# RK05TA.net
KiCad netlist of a schematic drawn in EAGLE
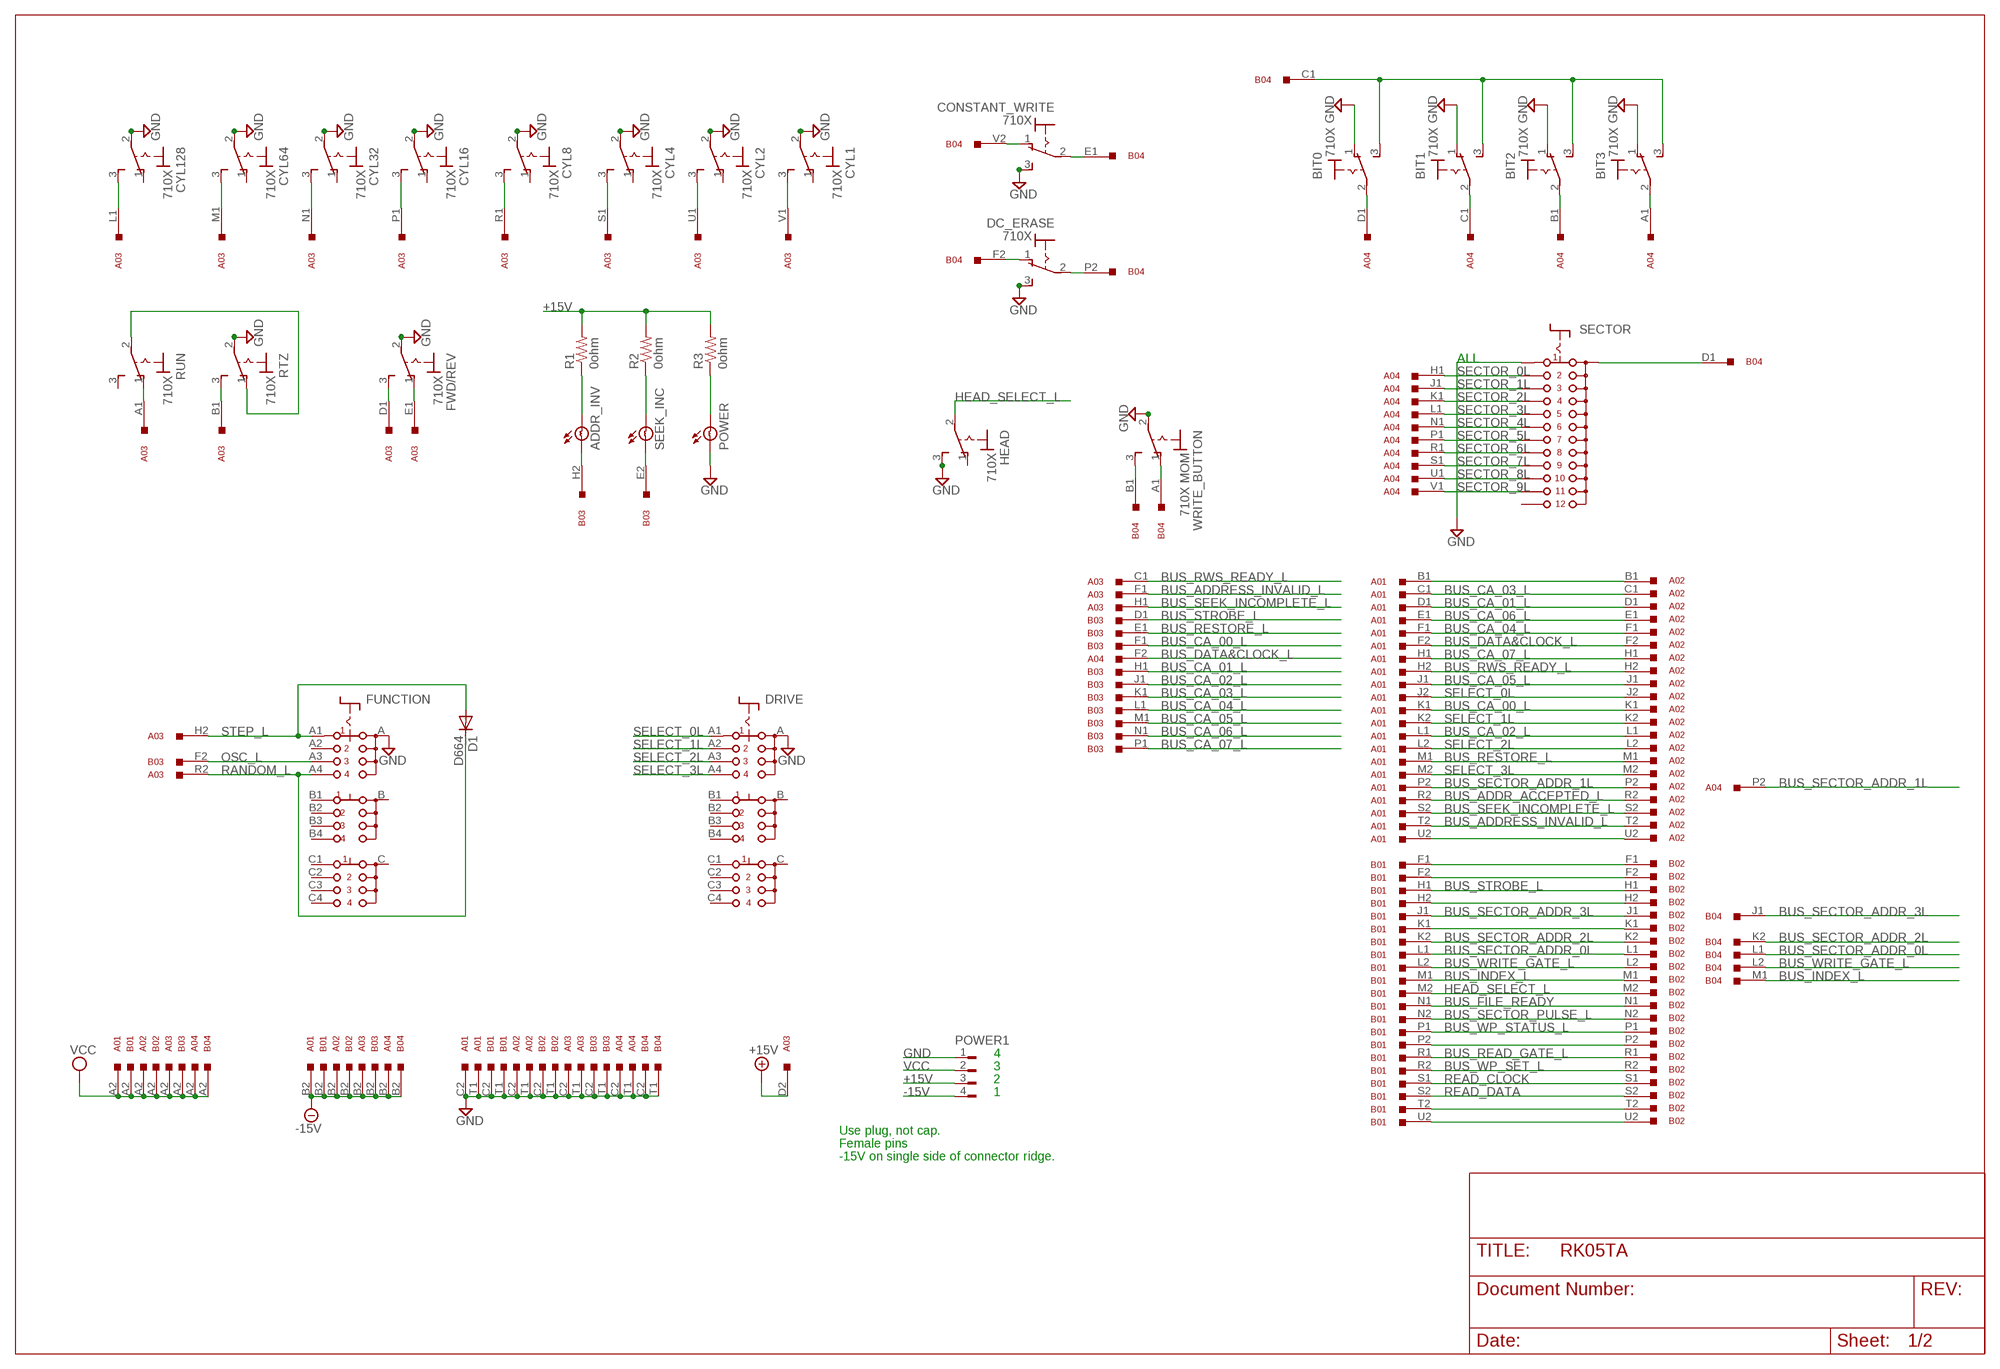
[diagram p0: schematic, sheet 1]
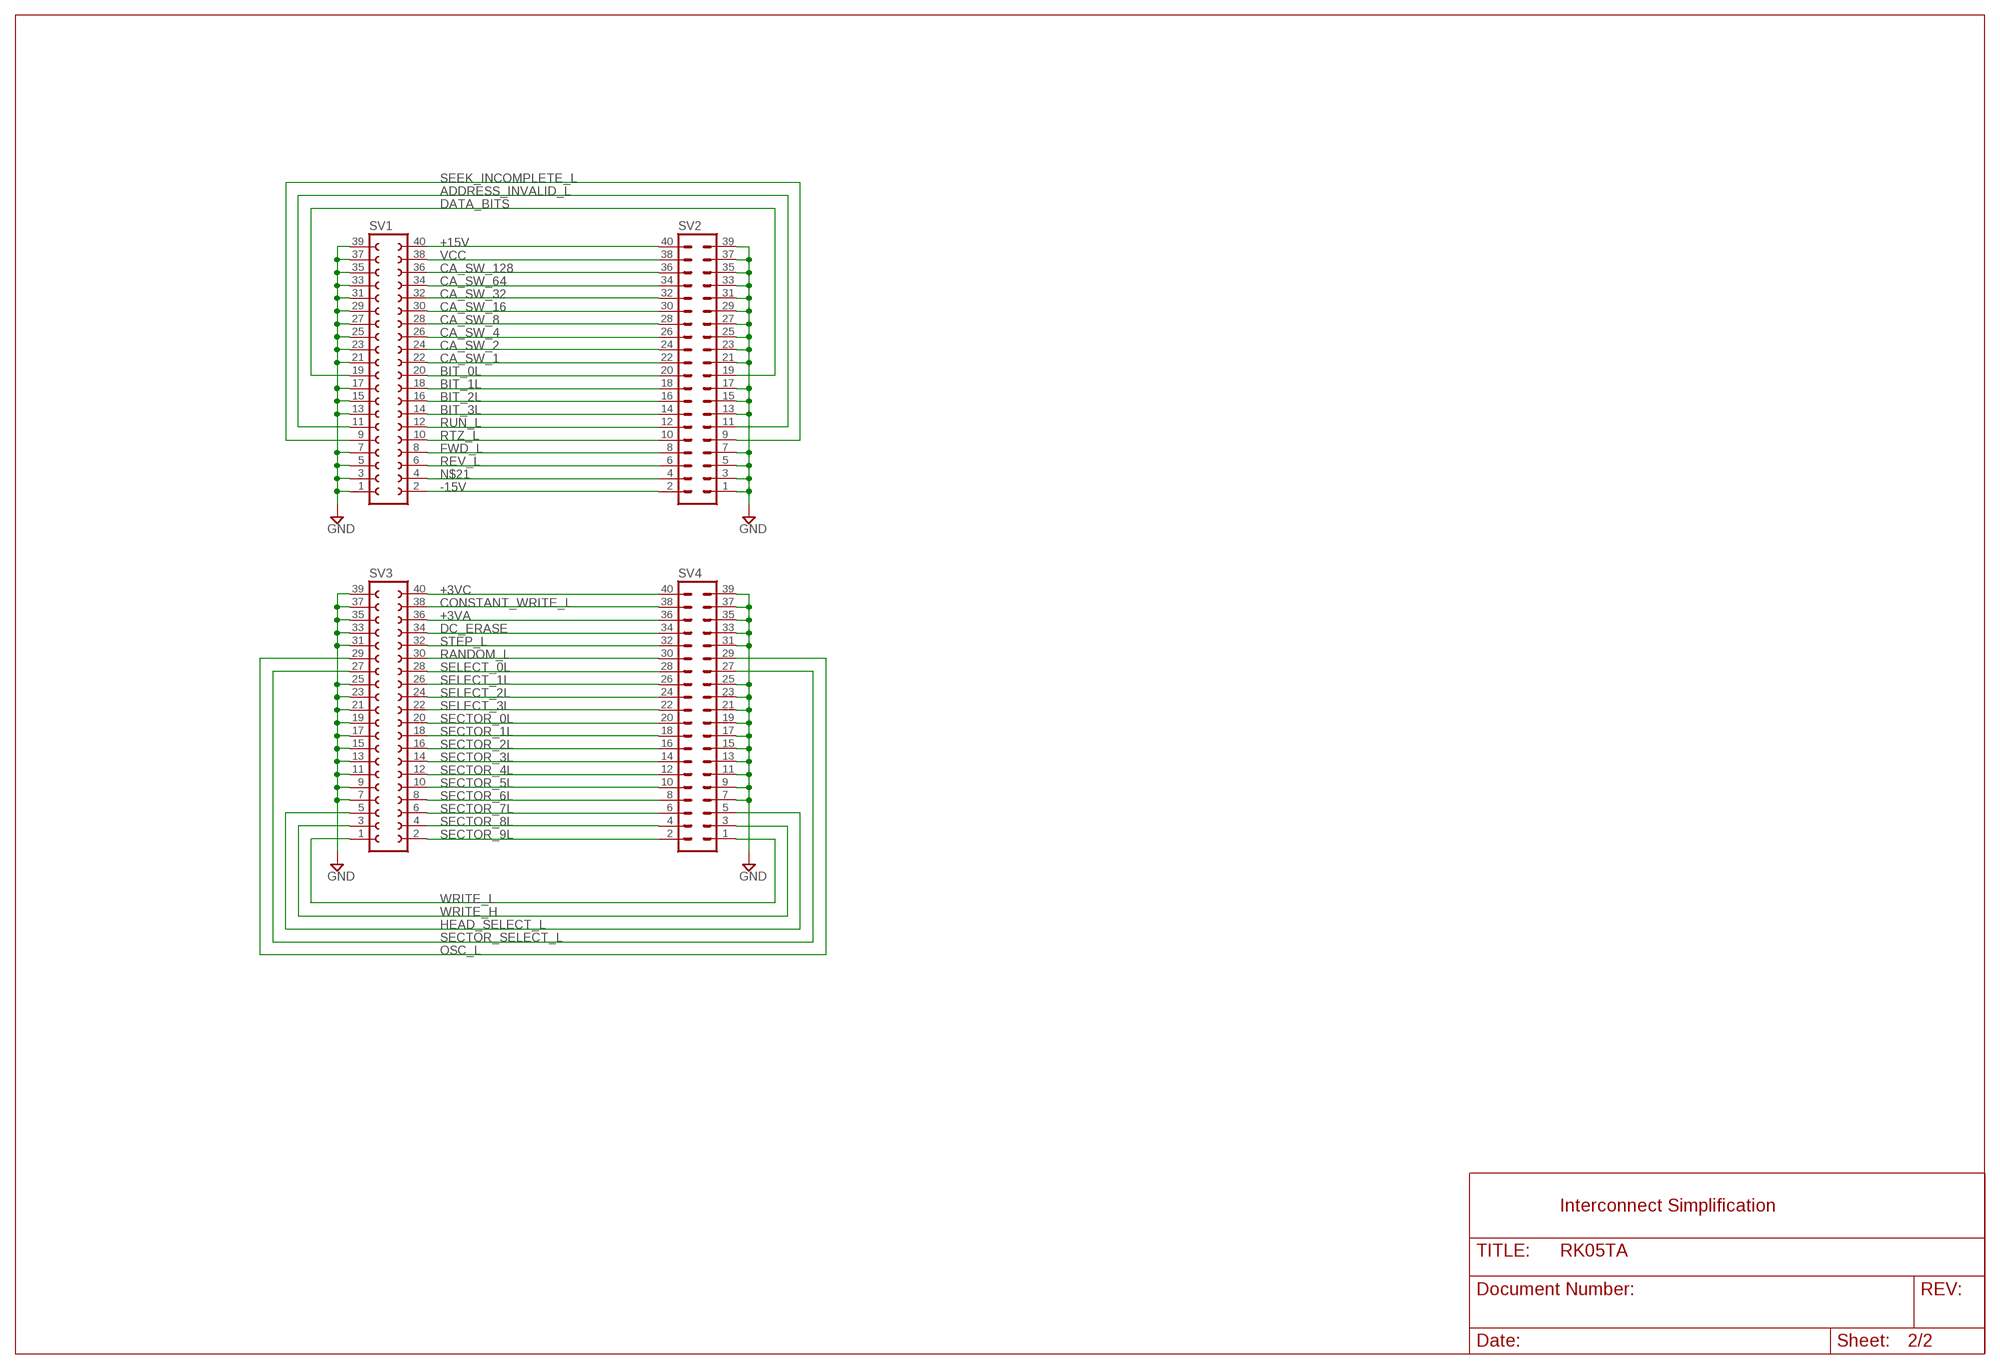
[diagram p1: schematic, sheet 2]

(export (version "E")
  (design (tool "Eeschema 10.0.6"))
  (components
    (comp (ref "SV1")
      (value "FE20-2W")
      (footprint "eagle-import:FE20-2W")
      (libsource (lib "eagle-import") (part "FE20-2W"))
    )
    (comp (ref "SV2")
      (value "MA20-2")
      (footprint "eagle-import:MA20-2")
      (libsource (lib "eagle-import") (part "MA20-2"))
    )
    (comp (ref "SV3")
      (value "FE20-2W")
      (footprint "eagle-import:FE20-2W")
      (libsource (lib "eagle-import") (part "FE20-2W"))
    )
    (comp (ref "SV4")
      (value "MA20-2")
      (footprint "eagle-import:MA20-2")
      (libsource (lib "eagle-import") (part "MA20-2"))
    )
    (comp (ref "A01")
      (value "BC11A")
      (footprint "eagle-import:H807")
      (libsource (lib "eagle-import") (part "M916"))
    )
    (comp (ref "A02")
      (value "M930")
      (footprint "eagle-import:H807")
      (libsource (lib "eagle-import") (part "M916"))
    )
    (comp (ref "A03")
      (value "G503")
      (footprint "eagle-import:H807")
      (libsource (lib "eagle-import") (part "M916"))
    )
    (comp (ref "A04")
      (value "G502")
      (footprint "eagle-import:H807")
      (libsource (lib "eagle-import") (part "M916"))
    )
    (comp (ref "ADDR_INV")
      (value "BULB")
      (footprint "eagle-import:BULB")
      (libsource (lib "eagle-import") (part "BULB"))
    )
    (comp (ref "B01")
      (value "BC11A")
      (footprint "eagle-import:H807")
      (libsource (lib "eagle-import") (part "M916"))
    )
    (comp (ref "B02")
      (value "M930")
      (footprint "eagle-import:H807")
      (libsource (lib "eagle-import") (part "M916"))
    )
    (comp (ref "B03")
      (value "G503")
      (footprint "eagle-import:H807")
      (libsource (lib "eagle-import") (part "M916"))
    )
    (comp (ref "B04")
      (value "G502")
      (footprint "eagle-import:H807")
      (libsource (lib "eagle-import") (part "M916"))
    )
    (comp (ref "BIT0")
      (value "710X")
      (footprint "eagle-import:7109MD9V3")
      (libsource (lib "eagle-import") (part "710X"))
    )
    (comp (ref "BIT1")
      (value "710X")
      (footprint "eagle-import:7109MD9V3")
      (libsource (lib "eagle-import") (part "710X"))
    )
    (comp (ref "BIT2")
      (value "710X")
      (footprint "eagle-import:7109MD9V3")
      (libsource (lib "eagle-import") (part "710X"))
    )
    (comp (ref "BIT3")
      (value "710X")
      (footprint "eagle-import:7109MD9V3")
      (libsource (lib "eagle-import") (part "710X"))
    )
    (comp (ref "CONSTANT_WRITE")
      (value "710X")
      (footprint "eagle-import:7109MD9V3")
      (libsource (lib "eagle-import") (part "710X"))
    )
    (comp (ref "CYL1")
      (value "710X")
      (footprint "eagle-import:7109MD9V3")
      (libsource (lib "eagle-import") (part "710X"))
    )
    (comp (ref "CYL2")
      (value "710X")
      (footprint "eagle-import:7109MD9V3")
      (libsource (lib "eagle-import") (part "710X"))
    )
    (comp (ref "CYL4")
      (value "710X")
      (footprint "eagle-import:7109MD9V3")
      (libsource (lib "eagle-import") (part "710X"))
    )
    (comp (ref "CYL8")
      (value "710X")
      (footprint "eagle-import:7109MD9V3")
      (libsource (lib "eagle-import") (part "710X"))
    )
    (comp (ref "CYL16")
      (value "710X")
      (footprint "eagle-import:7109MD9V3")
      (libsource (lib "eagle-import") (part "710X"))
    )
    (comp (ref "CYL32")
      (value "710X")
      (footprint "eagle-import:7109MD9V3")
      (libsource (lib "eagle-import") (part "710X"))
    )
    (comp (ref "CYL64")
      (value "710X")
      (footprint "eagle-import:7109MD9V3")
      (libsource (lib "eagle-import") (part "710X"))
    )
    (comp (ref "CYL128")
      (value "710X")
      (footprint "eagle-import:7109MD9V3")
      (libsource (lib "eagle-import") (part "710X"))
    )
    (comp (ref "D1")
      (value "D664")
      (footprint "eagle-import:DO35-10")
      (libsource (lib "eagle-import") (part "1N4148DO35-10"))
    )
    (comp (ref "DC_ERASE")
      (value "710X")
      (footprint "eagle-import:7109MD9V3")
      (libsource (lib "eagle-import") (part "710X"))
    )
    (comp (ref "DRIVE")
      (value "CK103X04")
      (footprint "eagle-import:CK103X04")
      (libsource (lib "eagle-import") (part "CK103X04"))
    )
    (comp (ref "FUNCTION")
      (value "CK103X04")
      (footprint "eagle-import:CK103X04")
      (libsource (lib "eagle-import") (part "CK103X04"))
    )
    (comp (ref "FWD/REV")
      (value "710X")
      (footprint "eagle-import:7109MD9V3")
      (libsource (lib "eagle-import") (part "710X"))
    )
    (comp (ref "HEAD")
      (value "710X")
      (footprint "eagle-import:7109MD9V3")
      (libsource (lib "eagle-import") (part "710X"))
    )
    (comp (ref "POWER")
      (value "BULB")
      (footprint "eagle-import:BULB")
      (libsource (lib "eagle-import") (part "BULB"))
    )
    (comp (ref "POWER1")
      (value "FLOPPY-4")
      (footprint "eagle-import:FLOPPY-4")
      (libsource (lib "eagle-import") (part "FLOPPY-4"))
    )
    (comp (ref "R1")
      (value "0ohm")
      (footprint "eagle-import:0207_10")
      (libsource (lib "eagle-import") (part "R-US_0207/10"))
    )
    (comp (ref "R2")
      (value "0ohm")
      (footprint "eagle-import:0207_10")
      (libsource (lib "eagle-import") (part "R-US_0207/10"))
    )
    (comp (ref "R3")
      (value "0ohm")
      (footprint "eagle-import:0207_10")
      (libsource (lib "eagle-import") (part "R-US_0207/10"))
    )
    (comp (ref "RTZ")
      (value "710X")
      (footprint "eagle-import:7109MD9V3")
      (libsource (lib "eagle-import") (part "710X"))
    )
    (comp (ref "RUN")
      (value "710X")
      (footprint "eagle-import:7109MD9V3")
      (libsource (lib "eagle-import") (part "710X"))
    )
    (comp (ref "SECTOR")
      (value "CK101X12")
      (footprint "eagle-import:CK101X12")
      (libsource (lib "eagle-import") (part "CK101X12"))
    )
    (comp (ref "SEEK_INC")
      (value "BULB")
      (footprint "eagle-import:BULB")
      (libsource (lib "eagle-import") (part "BULB"))
    )
    (comp (ref "WRITE_BUTTON")
      (value "710X MOM")
      (footprint "eagle-import:7109MD9V3")
      (libsource (lib "eagle-import") (part "710X"))
    )
  )
  (nets
    (net (code "1") (name "+3VA") (class "Default")
      (node (ref "B04") (pin "F2") (pinfunction "P$2_F2") (pintype "bidirectional"))
      (node (ref "DC_ERASE") (pin "1") (pinfunction "O_1") (pintype "passive"))
      (node (ref "SV3") (pin "36") (pinfunction "36_36") (pintype "passive"))
      (node (ref "SV4") (pin "36") (pinfunction "36_36") (pintype "passive"))
    )
    (net (code "2") (name "+3VC") (class "Default")
      (node (ref "B04") (pin "V2") (pinfunction "P$2_V2") (pintype "bidirectional"))
      (node (ref "CONSTANT_WRITE") (pin "1") (pinfunction "O_1") (pintype "passive"))
      (node (ref "SV3") (pin "40") (pinfunction "40_40") (pintype "passive"))
      (node (ref "SV4") (pin "40") (pinfunction "40_40") (pintype "passive"))
    )
    (net (code "3") (name "+15V") (class "Default")
      (node (ref "A03") (pin "D2") (pinfunction "P$2_D2") (pintype "bidirectional"))
      (node (ref "POWER1") (pin "3") (pinfunction "3_3") (pintype "passive"))
      (node (ref "R1") (pin "2") (pinfunction "2_2") (pintype "passive"))
      (node (ref "R2") (pin "2") (pinfunction "2_2") (pintype "passive"))
      (node (ref "R3") (pin "2") (pinfunction "2_2") (pintype "passive"))
      (node (ref "SV1") (pin "40") (pinfunction "40_40") (pintype "passive"))
      (node (ref "SV2") (pin "40") (pinfunction "40_40") (pintype "passive"))
    )
    (net (code "4") (name "-15V") (class "Default")
      (node (ref "A01") (pin "B2") (pinfunction "P$2_B2") (pintype "bidirectional"))
      (node (ref "A02") (pin "B2") (pinfunction "P$2_B2") (pintype "bidirectional"))
      (node (ref "A03") (pin "B2") (pinfunction "P$2_B2") (pintype "bidirectional"))
      (node (ref "A04") (pin "B2") (pinfunction "P$2_B2") (pintype "bidirectional"))
      (node (ref "B01") (pin "B2") (pinfunction "P$2_B2") (pintype "bidirectional"))
      (node (ref "B02") (pin "B2") (pinfunction "P$2_B2") (pintype "bidirectional"))
      (node (ref "B03") (pin "B2") (pinfunction "P$2_B2") (pintype "bidirectional"))
      (node (ref "B04") (pin "B2") (pinfunction "P$2_B2") (pintype "bidirectional"))
      (node (ref "POWER1") (pin "4") (pinfunction "4_4") (pintype "passive"))
      (node (ref "SV1") (pin "2") (pinfunction "2_2") (pintype "passive"))
      (node (ref "SV2") (pin "2") (pinfunction "2_2") (pintype "passive"))
    )
    (net (code "5") (name "ADDRESS_INVALID_L") (class "Default")
      (node (ref "ADDR_INV") (pin "B") (pinfunction "B_B") (pintype "passive"))
      (node (ref "B03") (pin "H2") (pinfunction "P$2_H2") (pintype "bidirectional"))
      (node (ref "SV1") (pin "11") (pinfunction "11_11") (pintype "passive"))
      (node (ref "SV2") (pin "11") (pinfunction "11_11") (pintype "passive"))
    )
    (net (code "6") (name "BIT_0L") (class "Default")
      (node (ref "A04") (pin "D1") (pinfunction "P$2_D1") (pintype "bidirectional"))
      (node (ref "BIT0") (pin "2") (pinfunction "P_2") (pintype "passive"))
      (node (ref "SV1") (pin "20") (pinfunction "20_20") (pintype "passive"))
      (node (ref "SV2") (pin "20") (pinfunction "20_20") (pintype "passive"))
    )
    (net (code "7") (name "BIT_1L") (class "Default")
      (node (ref "A04") (pin "C1") (pinfunction "P$2_C1") (pintype "bidirectional"))
      (node (ref "BIT1") (pin "2") (pinfunction "P_2") (pintype "passive"))
      (node (ref "SV1") (pin "18") (pinfunction "18_18") (pintype "passive"))
      (node (ref "SV2") (pin "18") (pinfunction "18_18") (pintype "passive"))
    )
    (net (code "8") (name "BIT_2L") (class "Default")
      (node (ref "A04") (pin "B1") (pinfunction "P$2_B1") (pintype "bidirectional"))
      (node (ref "BIT2") (pin "2") (pinfunction "P_2") (pintype "passive"))
      (node (ref "SV1") (pin "16") (pinfunction "16_16") (pintype "passive"))
      (node (ref "SV2") (pin "16") (pinfunction "16_16") (pintype "passive"))
    )
    (net (code "9") (name "BIT_3L") (class "Default")
      (node (ref "A04") (pin "A1") (pinfunction "P$2_A1") (pintype "bidirectional"))
      (node (ref "BIT3") (pin "2") (pinfunction "P_2") (pintype "passive"))
      (node (ref "SV1") (pin "14") (pinfunction "14_14") (pintype "passive"))
      (node (ref "SV2") (pin "14") (pinfunction "14_14") (pintype "passive"))
    )
    (net (code "10") (name "BUS_ADDRESS_INVALID_L") (class "Default")
      (node (ref "A01") (pin "T2") (pinfunction "P$2_T2") (pintype "bidirectional"))
      (node (ref "A02") (pin "T2") (pinfunction "P$2_T2") (pintype "bidirectional"))
      (node (ref "A03") (pin "F1") (pinfunction "P$2_F1") (pintype "bidirectional"))
    )
    (net (code "11") (name "BUS_ADDR_ACCEPTED_L") (class "Default")
      (node (ref "A01") (pin "R2") (pinfunction "P$2_R2") (pintype "bidirectional"))
      (node (ref "A02") (pin "R2") (pinfunction "P$2_R2") (pintype "bidirectional"))
    )
    (net (code "12") (name "BUS_CA_00_L") (class "Default")
      (node (ref "A01") (pin "K1") (pinfunction "P$2_K1") (pintype "bidirectional"))
      (node (ref "A02") (pin "K1") (pinfunction "P$2_K1") (pintype "bidirectional"))
      (node (ref "B03") (pin "F1") (pinfunction "P$2_F1") (pintype "bidirectional"))
    )
    (net (code "13") (name "BUS_CA_01_L") (class "Default")
      (node (ref "A01") (pin "D1") (pinfunction "P$2_D1") (pintype "bidirectional"))
      (node (ref "A02") (pin "D1") (pinfunction "P$2_D1") (pintype "bidirectional"))
      (node (ref "B03") (pin "H1") (pinfunction "P$2_H1") (pintype "bidirectional"))
    )
    (net (code "14") (name "BUS_CA_02_L") (class "Default")
      (node (ref "A01") (pin "L1") (pinfunction "P$2_L1") (pintype "bidirectional"))
      (node (ref "A02") (pin "L1") (pinfunction "P$2_L1") (pintype "bidirectional"))
      (node (ref "B03") (pin "J1") (pinfunction "P$2_J1") (pintype "bidirectional"))
    )
    (net (code "15") (name "BUS_CA_03_L") (class "Default")
      (node (ref "A01") (pin "C1") (pinfunction "P$2_C1") (pintype "bidirectional"))
      (node (ref "A02") (pin "C1") (pinfunction "P$2_C1") (pintype "bidirectional"))
      (node (ref "B03") (pin "K1") (pinfunction "P$2_K1") (pintype "bidirectional"))
    )
    (net (code "16") (name "BUS_CA_04_L") (class "Default")
      (node (ref "A01") (pin "F1") (pinfunction "P$2_F1") (pintype "bidirectional"))
      (node (ref "A02") (pin "F1") (pinfunction "P$2_F1") (pintype "bidirectional"))
      (node (ref "B03") (pin "L1") (pinfunction "P$2_L1") (pintype "bidirectional"))
    )
    (net (code "17") (name "BUS_CA_05_L") (class "Default")
      (node (ref "A01") (pin "J1") (pinfunction "P$2_J1") (pintype "bidirectional"))
      (node (ref "A02") (pin "J1") (pinfunction "P$2_J1") (pintype "bidirectional"))
      (node (ref "B03") (pin "M1") (pinfunction "P$2_M1") (pintype "bidirectional"))
    )
    (net (code "18") (name "BUS_CA_06_L") (class "Default")
      (node (ref "A01") (pin "E1") (pinfunction "P$2_E1") (pintype "bidirectional"))
      (node (ref "A02") (pin "E1") (pinfunction "P$2_E1") (pintype "bidirectional"))
      (node (ref "B03") (pin "N1") (pinfunction "P$2_N1") (pintype "bidirectional"))
    )
    (net (code "19") (name "BUS_CA_07_L") (class "Default")
      (node (ref "A01") (pin "H1") (pinfunction "P$2_H1") (pintype "bidirectional"))
      (node (ref "A02") (pin "H1") (pinfunction "P$2_H1") (pintype "bidirectional"))
      (node (ref "B03") (pin "P1") (pinfunction "P$2_P1") (pintype "bidirectional"))
    )
    (net (code "20") (name "BUS_DATA&CLOCK_L") (class "Default")
      (node (ref "A01") (pin "F2") (pinfunction "P$2_F2") (pintype "bidirectional"))
      (node (ref "A02") (pin "F2") (pinfunction "P$2_F2") (pintype "bidirectional"))
      (node (ref "A04") (pin "F2") (pinfunction "P$2_F2") (pintype "bidirectional"))
    )
    (net (code "21") (name "BUS_FILE_READY") (class "Default")
      (node (ref "B01") (pin "N1") (pinfunction "P$2_N1") (pintype "bidirectional"))
      (node (ref "B02") (pin "N1") (pinfunction "P$2_N1") (pintype "bidirectional"))
    )
    (net (code "22") (name "BUS_INDEX_L") (class "Default")
      (node (ref "B01") (pin "M1") (pinfunction "P$2_M1") (pintype "bidirectional"))
      (node (ref "B02") (pin "M1") (pinfunction "P$2_M1") (pintype "bidirectional"))
      (node (ref "B04") (pin "M1") (pinfunction "P$2_M1") (pintype "bidirectional"))
    )
    (net (code "23") (name "BUS_READ_GATE_L") (class "Default")
      (node (ref "B01") (pin "R1") (pinfunction "P$2_R1") (pintype "bidirectional"))
      (node (ref "B02") (pin "R1") (pinfunction "P$2_R1") (pintype "bidirectional"))
    )
    (net (code "24") (name "BUS_RESTORE_L") (class "Default")
      (node (ref "A01") (pin "M1") (pinfunction "P$2_M1") (pintype "bidirectional"))
      (node (ref "A02") (pin "M1") (pinfunction "P$2_M1") (pintype "bidirectional"))
      (node (ref "B03") (pin "E1") (pinfunction "P$2_E1") (pintype "bidirectional"))
    )
    (net (code "25") (name "BUS_RWS_READY_L") (class "Default")
      (node (ref "A01") (pin "H2") (pinfunction "P$2_H2") (pintype "bidirectional"))
      (node (ref "A02") (pin "H2") (pinfunction "P$2_H2") (pintype "bidirectional"))
      (node (ref "A03") (pin "C1") (pinfunction "P$2_C1") (pintype "bidirectional"))
    )
    (net (code "26") (name "BUS_SECTOR_ADDR_0L") (class "Default")
      (node (ref "B01") (pin "L1") (pinfunction "P$2_L1") (pintype "bidirectional"))
      (node (ref "B02") (pin "L1") (pinfunction "P$2_L1") (pintype "bidirectional"))
      (node (ref "B04") (pin "L1") (pinfunction "P$2_L1") (pintype "bidirectional"))
    )
    (net (code "27") (name "BUS_SECTOR_ADDR_1L") (class "Default")
      (node (ref "A01") (pin "P2") (pinfunction "P$2_P2") (pintype "bidirectional"))
      (node (ref "A02") (pin "P2") (pinfunction "P$2_P2") (pintype "bidirectional"))
      (node (ref "A04") (pin "P2") (pinfunction "P$2_P2") (pintype "bidirectional"))
    )
    (net (code "28") (name "BUS_SECTOR_ADDR_2L") (class "Default")
      (node (ref "B01") (pin "K2") (pinfunction "P$2_K2") (pintype "bidirectional"))
      (node (ref "B02") (pin "K2") (pinfunction "P$2_K2") (pintype "bidirectional"))
      (node (ref "B04") (pin "K2") (pinfunction "P$2_K2") (pintype "bidirectional"))
    )
    (net (code "29") (name "BUS_SECTOR_ADDR_3L") (class "Default")
      (node (ref "B01") (pin "J1") (pinfunction "P$2_J1") (pintype "bidirectional"))
      (node (ref "B02") (pin "J1") (pinfunction "P$2_J1") (pintype "bidirectional"))
      (node (ref "B04") (pin "J1") (pinfunction "P$2_J1") (pintype "bidirectional"))
    )
    (net (code "30") (name "BUS_SECTOR_PULSE_L") (class "Default")
      (node (ref "B01") (pin "N2") (pinfunction "P$2_N2") (pintype "bidirectional"))
      (node (ref "B02") (pin "N2") (pinfunction "P$2_N2") (pintype "bidirectional"))
    )
    (net (code "31") (name "BUS_SEEK_INCOMPLETE_L") (class "Default")
      (node (ref "A01") (pin "S2") (pinfunction "P$2_S2") (pintype "bidirectional"))
      (node (ref "A02") (pin "S2") (pinfunction "P$2_S2") (pintype "bidirectional"))
      (node (ref "A03") (pin "H1") (pinfunction "P$2_H1") (pintype "bidirectional"))
    )
    (net (code "32") (name "BUS_STROBE_L") (class "Default")
      (node (ref "B01") (pin "H1") (pinfunction "P$2_H1") (pintype "bidirectional"))
      (node (ref "B02") (pin "H1") (pinfunction "P$2_H1") (pintype "bidirectional"))
      (node (ref "B03") (pin "D1") (pinfunction "P$2_D1") (pintype "bidirectional"))
    )
    (net (code "33") (name "BUS_WP_SET_L") (class "Default")
      (node (ref "B01") (pin "R2") (pinfunction "P$2_R2") (pintype "bidirectional"))
      (node (ref "B02") (pin "R2") (pinfunction "P$2_R2") (pintype "bidirectional"))
    )
    (net (code "34") (name "BUS_WP_STATUS_L") (class "Default")
      (node (ref "B01") (pin "P1") (pinfunction "P$2_P1") (pintype "bidirectional"))
      (node (ref "B02") (pin "P1") (pinfunction "P$2_P1") (pintype "bidirectional"))
    )
    (net (code "35") (name "BUS_WRITE_GATE_L") (class "Default")
      (node (ref "B01") (pin "L2") (pinfunction "P$2_L2") (pintype "bidirectional"))
      (node (ref "B02") (pin "L2") (pinfunction "P$2_L2") (pintype "bidirectional"))
      (node (ref "B04") (pin "L2") (pinfunction "P$2_L2") (pintype "bidirectional"))
    )
    (net (code "36") (name "CA_SW_1") (class "Default")
      (node (ref "A03") (pin "V1") (pinfunction "P$2_V1") (pintype "bidirectional"))
      (node (ref "CYL1") (pin "3") (pinfunction "S_3") (pintype "passive"))
      (node (ref "SV1") (pin "22") (pinfunction "22_22") (pintype "passive"))
      (node (ref "SV2") (pin "22") (pinfunction "22_22") (pintype "passive"))
    )
    (net (code "37") (name "CA_SW_2") (class "Default")
      (node (ref "A03") (pin "U1") (pinfunction "P$2_U1") (pintype "bidirectional"))
      (node (ref "CYL2") (pin "3") (pinfunction "S_3") (pintype "passive"))
      (node (ref "SV1") (pin "24") (pinfunction "24_24") (pintype "passive"))
      (node (ref "SV2") (pin "24") (pinfunction "24_24") (pintype "passive"))
    )
    (net (code "38") (name "CA_SW_4") (class "Default")
      (node (ref "A03") (pin "S1") (pinfunction "P$2_S1") (pintype "bidirectional"))
      (node (ref "CYL4") (pin "3") (pinfunction "S_3") (pintype "passive"))
      (node (ref "SV1") (pin "26") (pinfunction "26_26") (pintype "passive"))
      (node (ref "SV2") (pin "26") (pinfunction "26_26") (pintype "passive"))
    )
    (net (code "39") (name "CA_SW_8") (class "Default")
      (node (ref "A03") (pin "R1") (pinfunction "P$2_R1") (pintype "bidirectional"))
      (node (ref "CYL8") (pin "3") (pinfunction "S_3") (pintype "passive"))
      (node (ref "SV1") (pin "28") (pinfunction "28_28") (pintype "passive"))
      (node (ref "SV2") (pin "28") (pinfunction "28_28") (pintype "passive"))
    )
    (net (code "40") (name "CA_SW_16") (class "Default")
      (node (ref "A03") (pin "P1") (pinfunction "P$2_P1") (pintype "bidirectional"))
      (node (ref "CYL16") (pin "3") (pinfunction "S_3") (pintype "passive"))
      (node (ref "SV1") (pin "30") (pinfunction "30_30") (pintype "passive"))
      (node (ref "SV2") (pin "30") (pinfunction "30_30") (pintype "passive"))
    )
    (net (code "41") (name "CA_SW_32") (class "Default")
      (node (ref "A03") (pin "N1") (pinfunction "P$2_N1") (pintype "bidirectional"))
      (node (ref "CYL32") (pin "3") (pinfunction "S_3") (pintype "passive"))
      (node (ref "SV1") (pin "32") (pinfunction "32_32") (pintype "passive"))
      (node (ref "SV2") (pin "32") (pinfunction "32_32") (pintype "passive"))
    )
    (net (code "42") (name "CA_SW_64") (class "Default")
      (node (ref "A03") (pin "M1") (pinfunction "P$2_M1") (pintype "bidirectional"))
      (node (ref "CYL64") (pin "3") (pinfunction "S_3") (pintype "passive"))
      (node (ref "SV1") (pin "34") (pinfunction "34_34") (pintype "passive"))
      (node (ref "SV2") (pin "34") (pinfunction "34_34") (pintype "passive"))
    )
    (net (code "43") (name "CA_SW_128") (class "Default")
      (node (ref "A03") (pin "L1") (pinfunction "P$2_L1") (pintype "bidirectional"))
      (node (ref "CYL128") (pin "3") (pinfunction "S_3") (pintype "passive"))
      (node (ref "SV1") (pin "36") (pinfunction "36_36") (pintype "passive"))
      (node (ref "SV2") (pin "36") (pinfunction "36_36") (pintype "passive"))
    )
    (net (code "44") (name "CONSTANT_WRITE_L") (class "Default")
      (node (ref "B04") (pin "E1") (pinfunction "P$2_E1") (pintype "bidirectional"))
      (node (ref "CONSTANT_WRITE") (pin "2") (pinfunction "P_2") (pintype "passive"))
      (node (ref "SV3") (pin "38") (pinfunction "38_38") (pintype "passive"))
      (node (ref "SV4") (pin "38") (pinfunction "38_38") (pintype "passive"))
    )
    (net (code "45") (name "DATA_BITS") (class "Default")
      (node (ref "B04") (pin "C1") (pinfunction "P$2_C1") (pintype "bidirectional"))
      (node (ref "BIT0") (pin "3") (pinfunction "S_3") (pintype "passive"))
      (node (ref "BIT1") (pin "3") (pinfunction "S_3") (pintype "passive"))
      (node (ref "BIT2") (pin "3") (pinfunction "S_3") (pintype "passive"))
      (node (ref "BIT3") (pin "3") (pinfunction "S_3") (pintype "passive"))
      (node (ref "SV1") (pin "19") (pinfunction "19_19") (pintype "passive"))
      (node (ref "SV2") (pin "19") (pinfunction "19_19") (pintype "passive"))
    )
    (net (code "46") (name "DC_ERASE") (class "Default")
      (node (ref "B04") (pin "P2") (pinfunction "P$2_P2") (pintype "bidirectional"))
      (node (ref "DC_ERASE") (pin "2") (pinfunction "P_2") (pintype "passive"))
      (node (ref "SV3") (pin "34") (pinfunction "34_34") (pintype "passive"))
      (node (ref "SV4") (pin "34") (pinfunction "34_34") (pintype "passive"))
    )
    (net (code "47") (name "FWD_L") (class "Default")
      (node (ref "A03") (pin "D1") (pinfunction "P$2_D1") (pintype "bidirectional"))
      (node (ref "FWD/REV") (pin "3") (pinfunction "S_3") (pintype "passive"))
      (node (ref "SV1") (pin "8") (pinfunction "8_8") (pintype "passive"))
      (node (ref "SV2") (pin "8") (pinfunction "8_8") (pintype "passive"))
    )
    (net (code "48") (name "GND") (class "Default")
      (node (ref "A01") (pin "C2") (pinfunction "P$2_C2") (pintype "bidirectional"))
      (node (ref "A01") (pin "T1") (pinfunction "P$2_T1") (pintype "bidirectional"))
      (node (ref "A02") (pin "C2") (pinfunction "P$2_C2") (pintype "bidirectional"))
      (node (ref "A02") (pin "T1") (pinfunction "P$2_T1") (pintype "bidirectional"))
      (node (ref "A03") (pin "C2") (pinfunction "P$2_C2") (pintype "bidirectional"))
      (node (ref "A03") (pin "T1") (pinfunction "P$2_T1") (pintype "bidirectional"))
      (node (ref "A04") (pin "C2") (pinfunction "P$2_C2") (pintype "bidirectional"))
      (node (ref "A04") (pin "T1") (pinfunction "P$2_T1") (pintype "bidirectional"))
      (node (ref "B01") (pin "C2") (pinfunction "P$2_C2") (pintype "bidirectional"))
      (node (ref "B01") (pin "T1") (pinfunction "P$2_T1") (pintype "bidirectional"))
      (node (ref "B02") (pin "C2") (pinfunction "P$2_C2") (pintype "bidirectional"))
      (node (ref "B02") (pin "T1") (pinfunction "P$2_T1") (pintype "bidirectional"))
      (node (ref "B03") (pin "C2") (pinfunction "P$2_C2") (pintype "bidirectional"))
      (node (ref "B03") (pin "T1") (pinfunction "P$2_T1") (pintype "bidirectional"))
      (node (ref "B04") (pin "C2") (pinfunction "P$2_C2") (pintype "bidirectional"))
      (node (ref "B04") (pin "T1") (pinfunction "P$2_T1") (pintype "bidirectional"))
      (node (ref "BIT0") (pin "1") (pinfunction "O_1") (pintype "passive"))
      (node (ref "BIT1") (pin "1") (pinfunction "O_1") (pintype "passive"))
      (node (ref "BIT2") (pin "1") (pinfunction "O_1") (pintype "passive"))
      (node (ref "BIT3") (pin "1") (pinfunction "O_1") (pintype "passive"))
      (node (ref "CONSTANT_WRITE") (pin "3") (pinfunction "S_3") (pintype "passive"))
      (node (ref "CYL1") (pin "2") (pinfunction "P_2") (pintype "passive"))
      (node (ref "CYL128") (pin "2") (pinfunction "P_2") (pintype "passive"))
      (node (ref "CYL16") (pin "2") (pinfunction "P_2") (pintype "passive"))
      (node (ref "CYL2") (pin "2") (pinfunction "P_2") (pintype "passive"))
      (node (ref "CYL32") (pin "2") (pinfunction "P_2") (pintype "passive"))
      (node (ref "CYL4") (pin "2") (pinfunction "P_2") (pintype "passive"))
      (node (ref "CYL64") (pin "2") (pinfunction "P_2") (pintype "passive"))
      (node (ref "CYL8") (pin "2") (pinfunction "P_2") (pintype "passive"))
      (node (ref "DC_ERASE") (pin "3") (pinfunction "S_3") (pintype "passive"))
      (node (ref "DRIVE") (pin "A") (pinfunction "A_A") (pintype "passive"))
      (node (ref "FUNCTION") (pin "A") (pinfunction "A_A") (pintype "passive"))
      (node (ref "FWD/REV") (pin "2") (pinfunction "P_2") (pintype "passive"))
      (node (ref "HEAD") (pin "3") (pinfunction "S_3") (pintype "passive"))
      (node (ref "POWER") (pin "B") (pinfunction "B_B") (pintype "passive"))
      (node (ref "POWER1") (pin "1") (pinfunction "1_1") (pintype "passive"))
      (node (ref "RTZ") (pin "2") (pinfunction "P_2") (pintype "passive"))
      (node (ref "SECTOR") (pin "1") (pinfunction "1_1") (pintype "passive"))
      (node (ref "SV1") (pin "1") (pinfunction "1_1") (pintype "passive"))
      (node (ref "SV1") (pin "13") (pinfunction "13_13") (pintype "passive"))
      (node (ref "SV1") (pin "15") (pinfunction "15_15") (pintype "passive"))
      (node (ref "SV1") (pin "17") (pinfunction "17_17") (pintype "passive"))
      (node (ref "SV1") (pin "21") (pinfunction "21_21") (pintype "passive"))
      (node (ref "SV1") (pin "23") (pinfunction "23_23") (pintype "passive"))
      (node (ref "SV1") (pin "25") (pinfunction "25_25") (pintype "passive"))
      (node (ref "SV1") (pin "27") (pinfunction "27_27") (pintype "passive"))
      (node (ref "SV1") (pin "29") (pinfunction "29_29") (pintype "passive"))
      (node (ref "SV1") (pin "3") (pinfunction "3_3") (pintype "passive"))
      (node (ref "SV1") (pin "31") (pinfunction "31_31") (pintype "passive"))
      (node (ref "SV1") (pin "33") (pinfunction "33_33") (pintype "passive"))
      (node (ref "SV1") (pin "35") (pinfunction "35_35") (pintype "passive"))
      (node (ref "SV1") (pin "37") (pinfunction "37_37") (pintype "passive"))
      (node (ref "SV1") (pin "39") (pinfunction "39_39") (pintype "passive"))
      (node (ref "SV1") (pin "5") (pinfunction "5_5") (pintype "passive"))
      (node (ref "SV1") (pin "7") (pinfunction "7_7") (pintype "passive"))
      (node (ref "SV2") (pin "1") (pinfunction "1_1") (pintype "passive"))
      (node (ref "SV2") (pin "13") (pinfunction "13_13") (pintype "passive"))
      (node (ref "SV2") (pin "15") (pinfunction "15_15") (pintype "passive"))
      (node (ref "SV2") (pin "17") (pinfunction "17_17") (pintype "passive"))
      (node (ref "SV2") (pin "21") (pinfunction "21_21") (pintype "passive"))
      (node (ref "SV2") (pin "23") (pinfunction "23_23") (pintype "passive"))
      (node (ref "SV2") (pin "25") (pinfunction "25_25") (pintype "passive"))
      (node (ref "SV2") (pin "27") (pinfunction "27_27") (pintype "passive"))
      (node (ref "SV2") (pin "29") (pinfunction "29_29") (pintype "passive"))
      (node (ref "SV2") (pin "3") (pinfunction "3_3") (pintype "passive"))
      (node (ref "SV2") (pin "31") (pinfunction "31_31") (pintype "passive"))
      (node (ref "SV2") (pin "33") (pinfunction "33_33") (pintype "passive"))
      (node (ref "SV2") (pin "35") (pinfunction "35_35") (pintype "passive"))
      (node (ref "SV2") (pin "37") (pinfunction "37_37") (pintype "passive"))
      (node (ref "SV2") (pin "39") (pinfunction "39_39") (pintype "passive"))
      (node (ref "SV2") (pin "5") (pinfunction "5_5") (pintype "passive"))
      (node (ref "SV2") (pin "7") (pinfunction "7_7") (pintype "passive"))
      (node (ref "SV3") (pin "11") (pinfunction "11_11") (pintype "passive"))
      (node (ref "SV3") (pin "13") (pinfunction "13_13") (pintype "passive"))
      (node (ref "SV3") (pin "15") (pinfunction "15_15") (pintype "passive"))
      (node (ref "SV3") (pin "17") (pinfunction "17_17") (pintype "passive"))
      (node (ref "SV3") (pin "19") (pinfunction "19_19") (pintype "passive"))
      (node (ref "SV3") (pin "21") (pinfunction "21_21") (pintype "passive"))
      (node (ref "SV3") (pin "23") (pinfunction "23_23") (pintype "passive"))
      (node (ref "SV3") (pin "25") (pinfunction "25_25") (pintype "passive"))
      (node (ref "SV3") (pin "31") (pinfunction "31_31") (pintype "passive"))
      (node (ref "SV3") (pin "33") (pinfunction "33_33") (pintype "passive"))
      (node (ref "SV3") (pin "35") (pinfunction "35_35") (pintype "passive"))
      (node (ref "SV3") (pin "37") (pinfunction "37_37") (pintype "passive"))
      (node (ref "SV3") (pin "39") (pinfunction "39_39") (pintype "passive"))
      (node (ref "SV3") (pin "7") (pinfunction "7_7") (pintype "passive"))
      (node (ref "SV3") (pin "9") (pinfunction "9_9") (pintype "passive"))
      (node (ref "SV4") (pin "11") (pinfunction "11_11") (pintype "passive"))
      (node (ref "SV4") (pin "13") (pinfunction "13_13") (pintype "passive"))
      (node (ref "SV4") (pin "15") (pinfunction "15_15") (pintype "passive"))
      (node (ref "SV4") (pin "17") (pinfunction "17_17") (pintype "passive"))
      (node (ref "SV4") (pin "19") (pinfunction "19_19") (pintype "passive"))
      (node (ref "SV4") (pin "21") (pinfunction "21_21") (pintype "passive"))
      (node (ref "SV4") (pin "23") (pinfunction "23_23") (pintype "passive"))
      (node (ref "SV4") (pin "25") (pinfunction "25_25") (pintype "passive"))
      (node (ref "SV4") (pin "31") (pinfunction "31_31") (pintype "passive"))
      (node (ref "SV4") (pin "33") (pinfunction "33_33") (pintype "passive"))
      (node (ref "SV4") (pin "35") (pinfunction "35_35") (pintype "passive"))
      (node (ref "SV4") (pin "37") (pinfunction "37_37") (pintype "passive"))
      (node (ref "SV4") (pin "39") (pinfunction "39_39") (pintype "passive"))
      (node (ref "SV4") (pin "7") (pinfunction "7_7") (pintype "passive"))
      (node (ref "SV4") (pin "9") (pinfunction "9_9") (pintype "passive"))
      (node (ref "WRITE_BUTTON") (pin "2") (pinfunction "P_2") (pintype "passive"))
    )
    (net (code "49") (name "HEAD_SELECT_L") (class "Default")
      (node (ref "B01") (pin "M2") (pinfunction "P$2_M2") (pintype "bidirectional"))
      (node (ref "B02") (pin "M2") (pinfunction "P$2_M2") (pintype "bidirectional"))
      (node (ref "HEAD") (pin "2") (pinfunction "P_2") (pintype "passive"))
      (node (ref "SV3") (pin "5") (pinfunction "5_5") (pintype "passive"))
      (node (ref "SV4") (pin "5") (pinfunction "5_5") (pintype "passive"))
    )
    (net (code "50") (name "N$21") (class "Default")
      (node (ref "SV1") (pin "4") (pinfunction "4_4") (pintype "passive"))
      (node (ref "SV2") (pin "4") (pinfunction "4_4") (pintype "passive"))
    )
    (net (code "51") (name "Net-(A01AH-P$2)") (class "Default")
      (node (ref "A01") (pin "U2") (pinfunction "P$2_U2") (pintype "bidirectional"))
      (node (ref "A02") (pin "U2") (pinfunction "P$2_U2") (pintype "bidirectional"))
    )
    (net (code "52") (name "Net-(A01C-P$2)") (class "Default")
      (node (ref "A01") (pin "B1") (pinfunction "P$2_B1") (pintype "bidirectional"))
      (node (ref "A02") (pin "B1") (pinfunction "P$2_B1") (pintype "bidirectional"))
    )
    (net (code "53") (name "Net-(ADDR_INV-PadA)") (class "Default")
      (node (ref "ADDR_INV") (pin "A") (pinfunction "A_A") (pintype "passive"))
      (node (ref "R1") (pin "1") (pinfunction "1_1") (pintype "passive"))
    )
    (net (code "54") (name "Net-(B01AF-P$2)") (class "Default")
      (node (ref "B01") (pin "T2") (pinfunction "P$2_T2") (pintype "bidirectional"))
      (node (ref "B02") (pin "T2") (pinfunction "P$2_T2") (pintype "bidirectional"))
    )
    (net (code "55") (name "Net-(B01AH-P$2)") (class "Default")
      (node (ref "B01") (pin "U2") (pinfunction "P$2_U2") (pintype "bidirectional"))
      (node (ref "B02") (pin "U2") (pinfunction "P$2_U2") (pintype "bidirectional"))
    )
    (net (code "56") (name "Net-(B01K-P$2)") (class "Default")
      (node (ref "B01") (pin "F1") (pinfunction "P$2_F1") (pintype "bidirectional"))
      (node (ref "B02") (pin "F1") (pinfunction "P$2_F1") (pintype "bidirectional"))
    )
    (net (code "57") (name "Net-(B01L-P$2)") (class "Default")
      (node (ref "B01") (pin "F2") (pinfunction "P$2_F2") (pintype "bidirectional"))
      (node (ref "B02") (pin "F2") (pinfunction "P$2_F2") (pintype "bidirectional"))
    )
    (net (code "58") (name "Net-(B01N-P$2)") (class "Default")
      (node (ref "B01") (pin "H2") (pinfunction "P$2_H2") (pintype "bidirectional"))
      (node (ref "B02") (pin "H2") (pinfunction "P$2_H2") (pintype "bidirectional"))
    )
    (net (code "59") (name "Net-(B01Q-P$2)") (class "Default")
      (node (ref "B01") (pin "K1") (pinfunction "P$2_K1") (pintype "bidirectional"))
      (node (ref "B02") (pin "K1") (pinfunction "P$2_K1") (pintype "bidirectional"))
    )
    (net (code "60") (name "Net-(B01Z-P$2)") (class "Default")
      (node (ref "B01") (pin "P2") (pinfunction "P$2_P2") (pintype "bidirectional"))
      (node (ref "B02") (pin "P2") (pinfunction "P$2_P2") (pintype "bidirectional"))
    )
    (net (code "61") (name "Net-(POWER-PadA)") (class "Default")
      (node (ref "POWER") (pin "A") (pinfunction "A_A") (pintype "passive"))
      (node (ref "R3") (pin "1") (pinfunction "1_1") (pintype "passive"))
    )
    (net (code "62") (name "Net-(R2-Pad1)") (class "Default")
      (node (ref "R2") (pin "1") (pinfunction "1_1") (pintype "passive"))
      (node (ref "SEEK_INC") (pin "A") (pinfunction "A_A") (pintype "passive"))
    )
    (net (code "63") (name "Net-(RTZA-O)") (class "Default")
      (node (ref "RTZ") (pin "1") (pinfunction "O_1") (pintype "passive"))
      (node (ref "RUN") (pin "2") (pinfunction "P_2") (pintype "passive"))
    )
    (net (code "64") (name "OSC_L") (class "Default")
      (node (ref "B03") (pin "F2") (pinfunction "P$2_F2") (pintype "bidirectional"))
      (node (ref "FUNCTION") (pin "A3") (pinfunction "A3_A3") (pintype "passive"))
      (node (ref "SV3") (pin "29") (pinfunction "29_29") (pintype "passive"))
      (node (ref "SV4") (pin "29") (pinfunction "29_29") (pintype "passive"))
    )
    (net (code "65") (name "RANDOM_L") (class "Default")
      (node (ref "A03") (pin "R2") (pinfunction "P$2_R2") (pintype "bidirectional"))
      (node (ref "D1") (pin "C") (pinfunction "C_C") (pintype "passive"))
      (node (ref "FUNCTION") (pin "A4") (pinfunction "A4_A4") (pintype "passive"))
      (node (ref "SV3") (pin "30") (pinfunction "30_30") (pintype "passive"))
      (node (ref "SV4") (pin "30") (pinfunction "30_30") (pintype "passive"))
    )
    (net (code "66") (name "READ_CLOCK") (class "Default")
      (node (ref "B01") (pin "S1") (pinfunction "P$2_S1") (pintype "bidirectional"))
      (node (ref "B02") (pin "S1") (pinfunction "P$2_S1") (pintype "bidirectional"))
    )
    (net (code "67") (name "READ_DATA") (class "Default")
      (node (ref "B01") (pin "S2") (pinfunction "P$2_S2") (pintype "bidirectional"))
      (node (ref "B02") (pin "S2") (pinfunction "P$2_S2") (pintype "bidirectional"))
    )
    (net (code "68") (name "REV_L") (class "Default")
      (node (ref "A03") (pin "E1") (pinfunction "P$2_E1") (pintype "bidirectional"))
      (node (ref "FWD/REV") (pin "1") (pinfunction "O_1") (pintype "passive"))
      (node (ref "SV1") (pin "6") (pinfunction "6_6") (pintype "passive"))
      (node (ref "SV2") (pin "6") (pinfunction "6_6") (pintype "passive"))
    )
    (net (code "69") (name "RTZ_L") (class "Default")
      (node (ref "A03") (pin "B1") (pinfunction "P$2_B1") (pintype "bidirectional"))
      (node (ref "RTZ") (pin "3") (pinfunction "S_3") (pintype "passive"))
      (node (ref "SV1") (pin "10") (pinfunction "10_10") (pintype "passive"))
      (node (ref "SV2") (pin "10") (pinfunction "10_10") (pintype "passive"))
    )
    (net (code "70") (name "RUN_L") (class "Default")
      (node (ref "A03") (pin "A1") (pinfunction "P$2_A1") (pintype "bidirectional"))
      (node (ref "RUN") (pin "1") (pinfunction "O_1") (pintype "passive"))
      (node (ref "SV1") (pin "12") (pinfunction "12_12") (pintype "passive"))
      (node (ref "SV2") (pin "12") (pinfunction "12_12") (pintype "passive"))
    )
    (net (code "71") (name "SECTOR_0L") (class "Default")
      (node (ref "A04") (pin "H1") (pinfunction "P$2_H1") (pintype "bidirectional"))
      (node (ref "SECTOR") (pin "2") (pinfunction "2_2") (pintype "passive"))
      (node (ref "SV3") (pin "20") (pinfunction "20_20") (pintype "passive"))
      (node (ref "SV4") (pin "20") (pinfunction "20_20") (pintype "passive"))
    )
    (net (code "72") (name "SECTOR_1L") (class "Default")
      (node (ref "A04") (pin "J1") (pinfunction "P$2_J1") (pintype "bidirectional"))
      (node (ref "SECTOR") (pin "3") (pinfunction "3_3") (pintype "passive"))
      (node (ref "SV3") (pin "18") (pinfunction "18_18") (pintype "passive"))
      (node (ref "SV4") (pin "18") (pinfunction "18_18") (pintype "passive"))
    )
    (net (code "73") (name "SECTOR_2L") (class "Default")
      (node (ref "A04") (pin "K1") (pinfunction "P$2_K1") (pintype "bidirectional"))
      (node (ref "SECTOR") (pin "4") (pinfunction "4_4") (pintype "passive"))
      (node (ref "SV3") (pin "16") (pinfunction "16_16") (pintype "passive"))
      (node (ref "SV4") (pin "16") (pinfunction "16_16") (pintype "passive"))
    )
    (net (code "74") (name "SECTOR_3L") (class "Default")
      (node (ref "A04") (pin "L1") (pinfunction "P$2_L1") (pintype "bidirectional"))
      (node (ref "SECTOR") (pin "5") (pinfunction "5_5") (pintype "passive"))
      (node (ref "SV3") (pin "14") (pinfunction "14_14") (pintype "passive"))
      (node (ref "SV4") (pin "14") (pinfunction "14_14") (pintype "passive"))
    )
    (net (code "75") (name "SECTOR_4L") (class "Default")
      (node (ref "A04") (pin "N1") (pinfunction "P$2_N1") (pintype "bidirectional"))
      (node (ref "SECTOR") (pin "6") (pinfunction "6_6") (pintype "passive"))
      (node (ref "SV3") (pin "12") (pinfunction "12_12") (pintype "passive"))
      (node (ref "SV4") (pin "12") (pinfunction "12_12") (pintype "passive"))
    )
    (net (code "76") (name "SECTOR_5L") (class "Default")
      (node (ref "A04") (pin "P1") (pinfunction "P$2_P1") (pintype "bidirectional"))
      (node (ref "SECTOR") (pin "7") (pinfunction "7_7") (pintype "passive"))
      (node (ref "SV3") (pin "10") (pinfunction "10_10") (pintype "passive"))
      (node (ref "SV4") (pin "10") (pinfunction "10_10") (pintype "passive"))
    )
    (net (code "77") (name "SECTOR_6L") (class "Default")
      (node (ref "A04") (pin "R1") (pinfunction "P$2_R1") (pintype "bidirectional"))
      (node (ref "SECTOR") (pin "8") (pinfunction "8_8") (pintype "passive"))
      (node (ref "SV3") (pin "8") (pinfunction "8_8") (pintype "passive"))
      (node (ref "SV4") (pin "8") (pinfunction "8_8") (pintype "passive"))
    )
    (net (code "78") (name "SECTOR_7L") (class "Default")
      (node (ref "A04") (pin "S1") (pinfunction "P$2_S1") (pintype "bidirectional"))
      (node (ref "SECTOR") (pin "9") (pinfunction "9_9") (pintype "passive"))
      (node (ref "SV3") (pin "6") (pinfunction "6_6") (pintype "passive"))
      (node (ref "SV4") (pin "6") (pinfunction "6_6") (pintype "passive"))
    )
    (net (code "79") (name "SECTOR_8L") (class "Default")
      (node (ref "A04") (pin "U1") (pinfunction "P$2_U1") (pintype "bidirectional"))
      (node (ref "SECTOR") (pin "10") (pinfunction "10_10") (pintype "passive"))
      (node (ref "SV3") (pin "4") (pinfunction "4_4") (pintype "passive"))
      (node (ref "SV4") (pin "4") (pinfunction "4_4") (pintype "passive"))
    )
    (net (code "80") (name "SECTOR_9L") (class "Default")
      (node (ref "A04") (pin "V1") (pinfunction "P$2_V1") (pintype "bidirectional"))
      (node (ref "SECTOR") (pin "11") (pinfunction "11_11") (pintype "passive"))
      (node (ref "SV3") (pin "2") (pinfunction "2_2") (pintype "passive"))
      (node (ref "SV4") (pin "2") (pinfunction "2_2") (pintype "passive"))
    )
    (net (code "81") (name "SECTOR_SELECT_L") (class "Default")
      (node (ref "B04") (pin "D1") (pinfunction "P$2_D1") (pintype "bidirectional"))
      (node (ref "SECTOR") (pin "A") (pinfunction "A_A") (pintype "passive"))
      (node (ref "SV3") (pin "27") (pinfunction "27_27") (pintype "passive"))
      (node (ref "SV4") (pin "27") (pinfunction "27_27") (pintype "passive"))
    )
    (net (code "82") (name "SEEK_INCOMPLETE_L") (class "Default")
      (node (ref "B03") (pin "E2") (pinfunction "P$2_E2") (pintype "bidirectional"))
      (node (ref "SEEK_INC") (pin "B") (pinfunction "B_B") (pintype "passive"))
      (node (ref "SV1") (pin "9") (pinfunction "9_9") (pintype "passive"))
      (node (ref "SV2") (pin "9") (pinfunction "9_9") (pintype "passive"))
    )
    (net (code "83") (name "SELECT_0L") (class "Default")
      (node (ref "A01") (pin "J2") (pinfunction "P$2_J2") (pintype "bidirectional"))
      (node (ref "A02") (pin "J2") (pinfunction "P$2_J2") (pintype "bidirectional"))
      (node (ref "DRIVE") (pin "A1") (pinfunction "A1_A1") (pintype "passive"))
      (node (ref "SV3") (pin "28") (pinfunction "28_28") (pintype "passive"))
      (node (ref "SV4") (pin "28") (pinfunction "28_28") (pintype "passive"))
    )
    (net (code "84") (name "SELECT_1L") (class "Default")
      (node (ref "A01") (pin "K2") (pinfunction "P$2_K2") (pintype "bidirectional"))
      (node (ref "A02") (pin "K2") (pinfunction "P$2_K2") (pintype "bidirectional"))
      (node (ref "DRIVE") (pin "A2") (pinfunction "A2_A2") (pintype "passive"))
      (node (ref "SV3") (pin "26") (pinfunction "26_26") (pintype "passive"))
      (node (ref "SV4") (pin "26") (pinfunction "26_26") (pintype "passive"))
    )
    (net (code "85") (name "SELECT_2L") (class "Default")
      (node (ref "A01") (pin "L2") (pinfunction "P$2_L2") (pintype "bidirectional"))
      (node (ref "A02") (pin "L2") (pinfunction "P$2_L2") (pintype "bidirectional"))
      (node (ref "DRIVE") (pin "A3") (pinfunction "A3_A3") (pintype "passive"))
      (node (ref "SV3") (pin "24") (pinfunction "24_24") (pintype "passive"))
      (node (ref "SV4") (pin "24") (pinfunction "24_24") (pintype "passive"))
    )
    (net (code "86") (name "SELECT_3L") (class "Default")
      (node (ref "A01") (pin "M2") (pinfunction "P$2_M2") (pintype "bidirectional"))
      (node (ref "A02") (pin "M2") (pinfunction "P$2_M2") (pintype "bidirectional"))
      (node (ref "DRIVE") (pin "A4") (pinfunction "A4_A4") (pintype "passive"))
      (node (ref "SV3") (pin "22") (pinfunction "22_22") (pintype "passive"))
      (node (ref "SV4") (pin "22") (pinfunction "22_22") (pintype "passive"))
    )
    (net (code "87") (name "STEP_L") (class "Default")
      (node (ref "A03") (pin "H2") (pinfunction "P$2_H2") (pintype "bidirectional"))
      (node (ref "D1") (pin "A") (pinfunction "A_A") (pintype "passive"))
      (node (ref "FUNCTION") (pin "A1") (pinfunction "A1_A1") (pintype "passive"))
      (node (ref "SV3") (pin "32") (pinfunction "32_32") (pintype "passive"))
      (node (ref "SV4") (pin "32") (pinfunction "32_32") (pintype "passive"))
    )
    (net (code "88") (name "VCC") (class "Default")
      (node (ref "A01") (pin "A2") (pinfunction "P$2_A2") (pintype "bidirectional"))
      (node (ref "A02") (pin "A2") (pinfunction "P$2_A2") (pintype "bidirectional"))
      (node (ref "A03") (pin "A2") (pinfunction "P$2_A2") (pintype "bidirectional"))
      (node (ref "A04") (pin "A2") (pinfunction "P$2_A2") (pintype "bidirectional"))
      (node (ref "B01") (pin "A2") (pinfunction "P$2_A2") (pintype "bidirectional"))
      (node (ref "B02") (pin "A2") (pinfunction "P$2_A2") (pintype "bidirectional"))
      (node (ref "B03") (pin "A2") (pinfunction "P$2_A2") (pintype "bidirectional"))
      (node (ref "B04") (pin "A2") (pinfunction "P$2_A2") (pintype "bidirectional"))
      (node (ref "POWER1") (pin "2") (pinfunction "2_2") (pintype "passive"))
      (node (ref "SV1") (pin "38") (pinfunction "38_38") (pintype "passive"))
      (node (ref "SV2") (pin "38") (pinfunction "38_38") (pintype "passive"))
    )
    (net (code "89") (name "WRITE_H") (class "Default")
      (node (ref "B04") (pin "A1") (pinfunction "P$2_A1") (pintype "bidirectional"))
      (node (ref "SV3") (pin "3") (pinfunction "3_3") (pintype "passive"))
      (node (ref "SV4") (pin "3") (pinfunction "3_3") (pintype "passive"))
      (node (ref "WRITE_BUTTON") (pin "1") (pinfunction "O_1") (pintype "passive"))
    )
    (net (code "90") (name "WRITE_L") (class "Default")
      (node (ref "B04") (pin "B1") (pinfunction "P$2_B1") (pintype "bidirectional"))
      (node (ref "SV3") (pin "1") (pinfunction "1_1") (pintype "passive"))
      (node (ref "SV4") (pin "1") (pinfunction "1_1") (pintype "passive"))
      (node (ref "WRITE_BUTTON") (pin "3") (pinfunction "S_3") (pintype "passive"))
    )
    (net (code "91") (name "unconnected-(CYL1A-O-Pad1)") (class "Default")
      (node (ref "CYL1") (pin "1") (pinfunction "O_1") (pintype "passive"))
    )
    (net (code "92") (name "unconnected-(CYL2A-O-Pad1)") (class "Default")
      (node (ref "CYL2") (pin "1") (pinfunction "O_1") (pintype "passive"))
    )
    (net (code "93") (name "unconnected-(CYL4A-O-Pad1)") (class "Default")
      (node (ref "CYL4") (pin "1") (pinfunction "O_1") (pintype "passive"))
    )
    (net (code "94") (name "unconnected-(CYL8A-O-Pad1)") (class "Default")
      (node (ref "CYL8") (pin "1") (pinfunction "O_1") (pintype "passive"))
    )
    (net (code "95") (name "unconnected-(CYL16A-O-Pad1)") (class "Default")
      (node (ref "CYL16") (pin "1") (pinfunction "O_1") (pintype "passive"))
    )
    (net (code "96") (name "unconnected-(CYL32A-O-Pad1)") (class "Default")
      (node (ref "CYL32") (pin "1") (pinfunction "O_1") (pintype "passive"))
    )
    (net (code "97") (name "unconnected-(CYL64A-O-Pad1)") (class "Default")
      (node (ref "CYL64") (pin "1") (pinfunction "O_1") (pintype "passive"))
    )
    (net (code "98") (name "unconnected-(CYL128A-O-Pad1)") (class "Default")
      (node (ref "CYL128") (pin "1") (pinfunction "O_1") (pintype "passive"))
    )
    (net (code "99") (name "unconnected-(DRIVE-PadB)") (class "Default")
      (node (ref "DRIVE") (pin "B") (pinfunction "B_B") (pintype "passive"))
    )
    (net (code "100") (name "unconnected-(DRIVE-PadB1)") (class "Default")
      (node (ref "DRIVE") (pin "B1") (pinfunction "B1_B1") (pintype "passive"))
    )
    (net (code "101") (name "unconnected-(DRIVE-PadB2)") (class "Default")
      (node (ref "DRIVE") (pin "B2") (pinfunction "B2_B2") (pintype "passive"))
    )
    (net (code "102") (name "unconnected-(DRIVE-PadB3)") (class "Default")
      (node (ref "DRIVE") (pin "B3") (pinfunction "B3_B3") (pintype "passive"))
    )
    (net (code "103") (name "unconnected-(DRIVE-PadB4)") (class "Default")
      (node (ref "DRIVE") (pin "B4") (pinfunction "B4_B4") (pintype "passive"))
    )
    (net (code "104") (name "unconnected-(DRIVE-PadC)") (class "Default")
      (node (ref "DRIVE") (pin "C") (pinfunction "C_C") (pintype "passive"))
    )
    (net (code "105") (name "unconnected-(DRIVE-PadC1)") (class "Default")
      (node (ref "DRIVE") (pin "C1") (pinfunction "C1_C1") (pintype "passive"))
    )
    (net (code "106") (name "unconnected-(DRIVE-PadC2)") (class "Default")
      (node (ref "DRIVE") (pin "C2") (pinfunction "C2_C2") (pintype "passive"))
    )
    (net (code "107") (name "unconnected-(DRIVE-PadC3)") (class "Default")
      (node (ref "DRIVE") (pin "C3") (pinfunction "C3_C3") (pintype "passive"))
    )
    (net (code "108") (name "unconnected-(DRIVE-PadC4)") (class "Default")
      (node (ref "DRIVE") (pin "C4") (pinfunction "C4_C4") (pintype "passive"))
    )
    (net (code "109") (name "unconnected-(FUNCTION-PadA2)") (class "Default")
      (node (ref "FUNCTION") (pin "A2") (pinfunction "A2_A2") (pintype "passive"))
    )
    (net (code "110") (name "unconnected-(FUNCTION-PadB)") (class "Default")
      (node (ref "FUNCTION") (pin "B") (pinfunction "B_B") (pintype "passive"))
    )
    (net (code "111") (name "unconnected-(FUNCTION-PadB1)") (class "Default")
      (node (ref "FUNCTION") (pin "B1") (pinfunction "B1_B1") (pintype "passive"))
    )
    (net (code "112") (name "unconnected-(FUNCTION-PadB2)") (class "Default")
      (node (ref "FUNCTION") (pin "B2") (pinfunction "B2_B2") (pintype "passive"))
    )
    (net (code "113") (name "unconnected-(FUNCTION-PadB3)") (class "Default")
      (node (ref "FUNCTION") (pin "B3") (pinfunction "B3_B3") (pintype "passive"))
    )
    (net (code "114") (name "unconnected-(FUNCTION-PadB4)") (class "Default")
      (node (ref "FUNCTION") (pin "B4") (pinfunction "B4_B4") (pintype "passive"))
    )
    (net (code "115") (name "unconnected-(FUNCTION-PadC)") (class "Default")
      (node (ref "FUNCTION") (pin "C") (pinfunction "C_C") (pintype "passive"))
    )
    (net (code "116") (name "unconnected-(FUNCTION-PadC1)") (class "Default")
      (node (ref "FUNCTION") (pin "C1") (pinfunction "C1_C1") (pintype "passive"))
    )
    (net (code "117") (name "unconnected-(FUNCTION-PadC2)") (class "Default")
      (node (ref "FUNCTION") (pin "C2") (pinfunction "C2_C2") (pintype "passive"))
    )
    (net (code "118") (name "unconnected-(FUNCTION-PadC3)") (class "Default")
      (node (ref "FUNCTION") (pin "C3") (pinfunction "C3_C3") (pintype "passive"))
    )
    (net (code "119") (name "unconnected-(FUNCTION-PadC4)") (class "Default")
      (node (ref "FUNCTION") (pin "C4") (pinfunction "C4_C4") (pintype "passive"))
    )
    (net (code "120") (name "unconnected-(HEADA-O-Pad1)") (class "Default")
      (node (ref "HEAD") (pin "1") (pinfunction "O_1") (pintype "passive"))
    )
    (net (code "121") (name "unconnected-(RUNA-S-Pad3)") (class "Default")
      (node (ref "RUN") (pin "3") (pinfunction "S_3") (pintype "passive"))
    )
    (net (code "122") (name "unconnected-(SECTOR-Pad12)") (class "Default")
      (node (ref "SECTOR") (pin "12") (pinfunction "12_12") (pintype "passive"))
    )
  )
)
